# schematic.net
KiCad netlist of a schematic drawn in Altium Designer
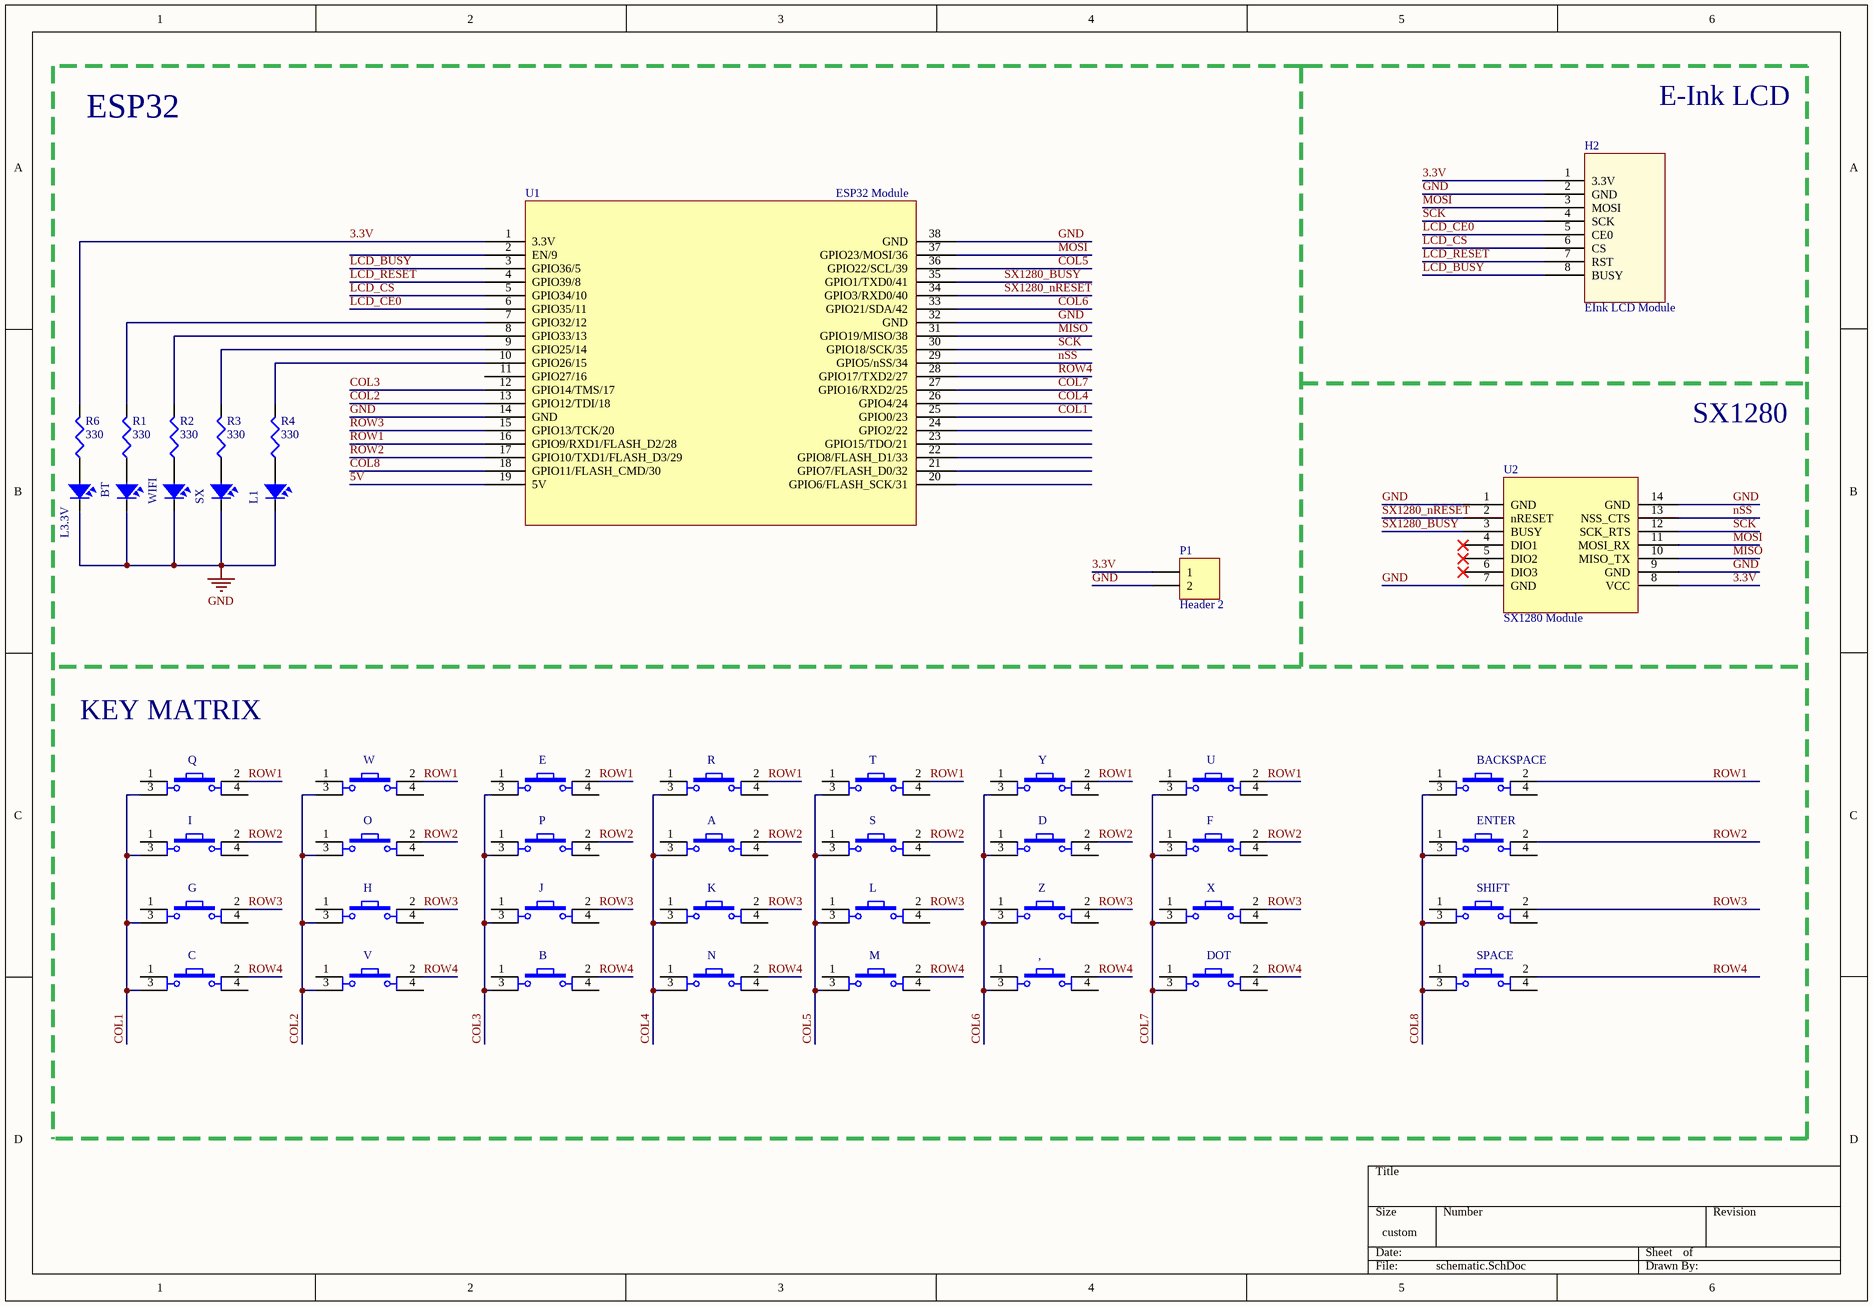
[diagram p0: schematic.SchDoc]

(export (version "E")
  (design (tool "Eeschema 10.0.6"))
  (components
    (comp (ref ",")
      (value "SW")
      (footprint "Kha_Button")
      (description "Switch button 4 pin")
      (libsource (lib "syhaunguyen") (part "SW4"))
    )
    (comp (ref "A")
      (value "SW")
      (footprint "Kha_Button")
      (description "Switch button 4 pin")
      (libsource (lib "syhaunguyen") (part "SW4"))
    )
    (comp (ref "B")
      (value "SW")
      (footprint "Kha_Button")
      (description "Switch button 4 pin")
      (libsource (lib "syhaunguyen") (part "SW4"))
    )
    (comp (ref "BACKSPACE")
      (value "SW")
      (footprint "Kha_Button")
      (description "Switch button 4 pin")
      (libsource (lib "syhaunguyen") (part "SW4"))
    )
    (comp (ref "BT")
      (value "LED SMD")
      (footprint "SM-LED-0805-Blue")
      (libsource (lib "syhaunguyen") (part "LED-SMD-0805"))
    )
    (comp (ref "C")
      (value "SW")
      (footprint "Kha_Button")
      (description "Switch button 4 pin")
      (libsource (lib "syhaunguyen") (part "SW4"))
    )
    (comp (ref "D")
      (value "SW")
      (footprint "Kha_Button")
      (description "Switch button 4 pin")
      (libsource (lib "syhaunguyen") (part "SW4"))
    )
    (comp (ref "DOT")
      (value "SW")
      (footprint "Kha_Button")
      (description "Switch button 4 pin")
      (libsource (lib "syhaunguyen") (part "SW4"))
    )
    (comp (ref "E")
      (value "SW")
      (footprint "Kha_Button")
      (description "Switch button 4 pin")
      (libsource (lib "syhaunguyen") (part "SW4"))
    )
    (comp (ref "ENTER")
      (value "SW")
      (footprint "Kha_Button")
      (description "Switch button 4 pin")
      (libsource (lib "syhaunguyen") (part "SW4"))
    )
    (comp (ref "F")
      (value "SW")
      (footprint "Kha_Button")
      (description "Switch button 4 pin")
      (libsource (lib "syhaunguyen") (part "SW4"))
    )
    (comp (ref "G")
      (value "SW")
      (footprint "Kha_Button")
      (description "Switch button 4 pin")
      (libsource (lib "syhaunguyen") (part "SW4"))
    )
    (comp (ref "H")
      (value "SW")
      (footprint "Kha_Button")
      (description "Switch button 4 pin")
      (libsource (lib "syhaunguyen") (part "SW4"))
    )
    (comp (ref "H2")
      (value "EInk LCD Module")
      (footprint "EInk_Module")
      (libsource (lib "EInk_Project_Lib") (part "E-Ink LCD"))
    )
    (comp (ref "I")
      (value "SW")
      (footprint "Kha_Button")
      (description "Switch button 4 pin")
      (libsource (lib "syhaunguyen") (part "SW4"))
    )
    (comp (ref "J")
      (value "SW")
      (footprint "Kha_Button")
      (description "Switch button 4 pin")
      (libsource (lib "syhaunguyen") (part "SW4"))
    )
    (comp (ref "K")
      (value "SW")
      (footprint "Kha_Button")
      (description "Switch button 4 pin")
      (libsource (lib "syhaunguyen") (part "SW4"))
    )
    (comp (ref "L")
      (value "SW")
      (footprint "Kha_Button")
      (description "Switch button 4 pin")
      (libsource (lib "syhaunguyen") (part "SW4"))
    )
    (comp (ref "L1")
      (value "LED SMD")
      (footprint "SM-LED-0805-Blue")
      (libsource (lib "syhaunguyen") (part "LED-SMD-0805"))
    )
    (comp (ref "L3.3V")
      (value "LED SMD")
      (footprint "SM-LED-0805-Blue")
      (libsource (lib "syhaunguyen") (part "LED-SMD-0805"))
    )
    (comp (ref "M")
      (value "SW")
      (footprint "Kha_Button")
      (description "Switch button 4 pin")
      (libsource (lib "syhaunguyen") (part "SW4"))
    )
    (comp (ref "N")
      (value "SW")
      (footprint "Kha_Button")
      (description "Switch button 4 pin")
      (libsource (lib "syhaunguyen") (part "SW4"))
    )
    (comp (ref "O")
      (value "SW")
      (footprint "Kha_Button")
      (description "Switch button 4 pin")
      (libsource (lib "syhaunguyen") (part "SW4"))
    )
    (comp (ref "P")
      (value "SW")
      (footprint "Kha_Button")
      (description "Switch button 4 pin")
      (libsource (lib "syhaunguyen") (part "SW4"))
    )
    (comp (ref "P1")
      (value "Header 2")
      (footprint "Header 2 SMT")
      (description "Header, 2-Pin")
      (fields (field (name "PUBLISHER") "Altium Limited"))
      (libsource (lib "Miscellaneous Connectors") (part "Header 2"))
    )
    (comp (ref "Q")
      (value "SW")
      (footprint "Kha_Button")
      (description "Switch button 4 pin")
      (libsource (lib "syhaunguyen") (part "SW4"))
    )
    (comp (ref "R")
      (value "SW")
      (footprint "Kha_Button")
      (description "Switch button 4 pin")
      (libsource (lib "syhaunguyen") (part "SW4"))
    )
    (comp (ref "R1")
      (value "330")
      (footprint "J1-0603")
      (description "Resistor")
      (fields (field (name "Comment") "Res3") (field (name "PUBLISHER") "Altium Limited"))
      (libsource (lib "Miscellaneous Devices") (part "Res3"))
    )
    (comp (ref "R2")
      (value "330")
      (footprint "J1-0603")
      (description "Resistor")
      (fields (field (name "Comment") "Res3") (field (name "PUBLISHER") "Altium Limited"))
      (libsource (lib "Miscellaneous Devices") (part "Res3"))
    )
    (comp (ref "R3")
      (value "330")
      (footprint "J1-0603")
      (description "Resistor")
      (fields (field (name "Comment") "Res3") (field (name "PUBLISHER") "Altium Limited"))
      (libsource (lib "Miscellaneous Devices") (part "Res3"))
    )
    (comp (ref "R4")
      (value "330")
      (footprint "J1-0603")
      (description "Resistor")
      (fields (field (name "Comment") "Res3") (field (name "PUBLISHER") "Altium Limited"))
      (libsource (lib "Miscellaneous Devices") (part "Res3"))
    )
    (comp (ref "R6")
      (value "330")
      (footprint "J1-0603")
      (description "Resistor")
      (fields (field (name "Comment") "Res3") (field (name "PUBLISHER") "Altium Limited"))
      (libsource (lib "Miscellaneous Devices") (part "Res3"))
    )
    (comp (ref "S")
      (value "SW")
      (footprint "Kha_Button")
      (description "Switch button 4 pin")
      (libsource (lib "syhaunguyen") (part "SW4"))
    )
    (comp (ref "SHIFT")
      (value "SW")
      (footprint "Kha_Button")
      (description "Switch button 4 pin")
      (libsource (lib "syhaunguyen") (part "SW4"))
    )
    (comp (ref "SPACE")
      (value "SW")
      (footprint "Kha_Button")
      (description "Switch button 4 pin")
      (libsource (lib "syhaunguyen") (part "SW4"))
    )
    (comp (ref "SX")
      (value "LED SMD")
      (footprint "SM-LED-0805-Blue")
      (libsource (lib "syhaunguyen") (part "LED-SMD-0805"))
    )
    (comp (ref "T")
      (value "SW")
      (footprint "Kha_Button")
      (description "Switch button 4 pin")
      (libsource (lib "syhaunguyen") (part "SW4"))
    )
    (comp (ref "U")
      (value "SW")
      (footprint "Kha_Button")
      (description "Switch button 4 pin")
      (libsource (lib "syhaunguyen") (part "SW4"))
    )
    (comp (ref "U1")
      (value "ESP32 Module")
      (footprint "ESP2 Module")
      (libsource (lib "EInk_Project_Lib") (part "ESP32_Module"))
    )
    (comp (ref "U2")
      (value "SX1280 Module")
      (footprint "SX1280 Module")
      (libsource (lib "EInk_Project_Lib") (part "SX1280 Module"))
    )
    (comp (ref "V")
      (value "SW")
      (footprint "Kha_Button")
      (description "Switch button 4 pin")
      (libsource (lib "syhaunguyen") (part "SW4"))
    )
    (comp (ref "W")
      (value "SW")
      (footprint "Kha_Button")
      (description "Switch button 4 pin")
      (libsource (lib "syhaunguyen") (part "SW4"))
    )
    (comp (ref "WIFI")
      (value "LED SMD")
      (footprint "SM-LED-0805-Blue")
      (libsource (lib "syhaunguyen") (part "LED-SMD-0805"))
    )
    (comp (ref "X")
      (value "SW")
      (footprint "Kha_Button")
      (description "Switch button 4 pin")
      (libsource (lib "syhaunguyen") (part "SW4"))
    )
    (comp (ref "Y")
      (value "SW")
      (footprint "Kha_Button")
      (description "Switch button 4 pin")
      (libsource (lib "syhaunguyen") (part "SW4"))
    )
    (comp (ref "Z")
      (value "SW")
      (footprint "Kha_Button")
      (description "Switch button 4 pin")
      (libsource (lib "syhaunguyen") (part "SW4"))
    )
  )
  (nets
    (net (code "1") (name "/3.3V") (class "Default")
      (node (ref "H2") (pin "1") (pinfunction "3.3V_1") (pintype "passive"))
      (node (ref "P1") (pin "1") (pinfunction "1_1") (pintype "passive"))
      (node (ref "R6") (pin "2") (pinfunction "2_2") (pintype "passive"))
      (node (ref "U1") (pin "1") (pinfunction "3.3V_1") (pintype "passive"))
      (node (ref "U2") (pin "8") (pinfunction "VCC_8") (pintype "passive"))
    )
    (net (code "2") (name "/5V") (class "Default")
      (node (ref "U1") (pin "19") (pinfunction "5V_19") (pintype "passive"))
    )
    (net (code "3") (name "/COL1") (class "Default")
      (node (ref "C") (pin "3") (pintype "passive"))
      (node (ref "G") (pin "3") (pintype "passive"))
      (node (ref "I") (pin "3") (pintype "passive"))
      (node (ref "Q") (pin "3") (pintype "passive"))
      (node (ref "U1") (pin "25") (pinfunction "GPIO0/23_25") (pintype "passive"))
    )
    (net (code "4") (name "/COL2") (class "Default")
      (node (ref "H") (pin "3") (pintype "passive"))
      (node (ref "O") (pin "3") (pintype "passive"))
      (node (ref "U1") (pin "13") (pinfunction "GPIO12/TDI/18_13") (pintype "passive"))
      (node (ref "V") (pin "3") (pintype "passive"))
      (node (ref "W") (pin "3") (pintype "passive"))
    )
    (net (code "5") (name "/COL3") (class "Default")
      (node (ref "B") (pin "3") (pintype "passive"))
      (node (ref "E") (pin "3") (pintype "passive"))
      (node (ref "J") (pin "3") (pintype "passive"))
      (node (ref "P") (pin "3") (pintype "passive"))
      (node (ref "U1") (pin "12") (pinfunction "GPIO14/TMS/17_12") (pintype "passive"))
    )
    (net (code "6") (name "/COL4") (class "Default")
      (node (ref "A") (pin "3") (pintype "passive"))
      (node (ref "K") (pin "3") (pintype "passive"))
      (node (ref "N") (pin "3") (pintype "passive"))
      (node (ref "R") (pin "3") (pintype "passive"))
      (node (ref "U1") (pin "26") (pinfunction "GPIO4/24_26") (pintype "passive"))
    )
    (net (code "7") (name "/COL5") (class "Default")
      (node (ref "L") (pin "3") (pintype "passive"))
      (node (ref "M") (pin "3") (pintype "passive"))
      (node (ref "S") (pin "3") (pintype "passive"))
      (node (ref "T") (pin "3") (pintype "passive"))
      (node (ref "U1") (pin "36") (pinfunction "GPIO22/SCL/39_36") (pintype "passive"))
    )
    (net (code "8") (name "/COL6") (class "Default")
      (node (ref ",") (pin "3") (pintype "passive"))
      (node (ref "D") (pin "3") (pintype "passive"))
      (node (ref "U1") (pin "33") (pinfunction "GPIO21/SDA/42_33") (pintype "passive"))
      (node (ref "Y") (pin "3") (pintype "passive"))
      (node (ref "Z") (pin "3") (pintype "passive"))
    )
    (net (code "9") (name "/COL7") (class "Default")
      (node (ref "DOT") (pin "3") (pintype "passive"))
      (node (ref "F") (pin "3") (pintype "passive"))
      (node (ref "U") (pin "3") (pintype "passive"))
      (node (ref "U1") (pin "27") (pinfunction "GPIO16/RXD2/25_27") (pintype "passive"))
      (node (ref "X") (pin "3") (pintype "passive"))
    )
    (net (code "10") (name "/COL8") (class "Default")
      (node (ref "BACKSPACE") (pin "3") (pintype "passive"))
      (node (ref "ENTER") (pin "3") (pintype "passive"))
      (node (ref "SHIFT") (pin "3") (pintype "passive"))
      (node (ref "SPACE") (pin "3") (pintype "passive"))
      (node (ref "U1") (pin "18") (pinfunction "GPIO11/FLASH_CMD/30_18") (pintype "passive"))
    )
    (net (code "11") (name "/LCD_BUSY") (class "Default")
      (node (ref "H2") (pin "8") (pinfunction "BUSY_8") (pintype "passive"))
      (node (ref "U1") (pin "3") (pinfunction "GPIO36/5_3") (pintype "passive"))
    )
    (net (code "12") (name "/LCD_CE0") (class "Default")
      (node (ref "H2") (pin "5") (pinfunction "CE0_5") (pintype "passive"))
      (node (ref "U1") (pin "6") (pinfunction "GPIO35/11_6") (pintype "passive"))
    )
    (net (code "13") (name "/LCD_CS") (class "Default")
      (node (ref "H2") (pin "6") (pinfunction "CS_6") (pintype "passive"))
      (node (ref "U1") (pin "5") (pinfunction "GPIO34/10_5") (pintype "passive"))
    )
    (net (code "14") (name "/LCD_RESET") (class "Default")
      (node (ref "H2") (pin "7") (pinfunction "RST_7") (pintype "passive"))
      (node (ref "U1") (pin "4") (pinfunction "GPIO39/8_4") (pintype "passive"))
    )
    (net (code "15") (name "/MISO") (class "Default")
      (node (ref "U1") (pin "31") (pinfunction "GPIO19/MISO/38_31") (pintype "passive"))
      (node (ref "U2") (pin "10") (pinfunction "MISO_TX_10") (pintype "passive"))
    )
    (net (code "16") (name "/MOSI") (class "Default")
      (node (ref "H2") (pin "3") (pinfunction "MOSI_3") (pintype "passive"))
      (node (ref "U1") (pin "37") (pinfunction "GPIO23/MOSI/36_37") (pintype "passive"))
      (node (ref "U2") (pin "11") (pinfunction "MOSI_RX_11") (pintype "passive"))
    )
    (net (code "17") (name "/ROW1") (class "Default")
      (node (ref "BACKSPACE") (pin "2") (pintype "passive"))
      (node (ref "E") (pin "2") (pintype "passive"))
      (node (ref "Q") (pin "2") (pintype "passive"))
      (node (ref "R") (pin "2") (pintype "passive"))
      (node (ref "T") (pin "2") (pintype "passive"))
      (node (ref "U") (pin "2") (pintype "passive"))
      (node (ref "U1") (pin "16") (pinfunction "GPIO9/RXD1/FLASH_D2/28_16") (pintype "passive"))
      (node (ref "W") (pin "2") (pintype "passive"))
      (node (ref "Y") (pin "2") (pintype "passive"))
    )
    (net (code "18") (name "/ROW2") (class "Default")
      (node (ref "A") (pin "2") (pintype "passive"))
      (node (ref "D") (pin "2") (pintype "passive"))
      (node (ref "ENTER") (pin "2") (pintype "passive"))
      (node (ref "F") (pin "2") (pintype "passive"))
      (node (ref "I") (pin "2") (pintype "passive"))
      (node (ref "O") (pin "2") (pintype "passive"))
      (node (ref "P") (pin "2") (pintype "passive"))
      (node (ref "S") (pin "2") (pintype "passive"))
      (node (ref "U1") (pin "17") (pinfunction "GPIO10/TXD1/FLASH_D3/29_17") (pintype "passive"))
    )
    (net (code "19") (name "/ROW3") (class "Default")
      (node (ref "G") (pin "2") (pintype "passive"))
      (node (ref "H") (pin "2") (pintype "passive"))
      (node (ref "J") (pin "2") (pintype "passive"))
      (node (ref "K") (pin "2") (pintype "passive"))
      (node (ref "L") (pin "2") (pintype "passive"))
      (node (ref "SHIFT") (pin "2") (pintype "passive"))
      (node (ref "U1") (pin "15") (pinfunction "GPIO13/TCK/20_15") (pintype "passive"))
      (node (ref "X") (pin "2") (pintype "passive"))
      (node (ref "Z") (pin "2") (pintype "passive"))
    )
    (net (code "20") (name "/ROW4") (class "Default")
      (node (ref ",") (pin "2") (pintype "passive"))
      (node (ref "B") (pin "2") (pintype "passive"))
      (node (ref "C") (pin "2") (pintype "passive"))
      (node (ref "DOT") (pin "2") (pintype "passive"))
      (node (ref "M") (pin "2") (pintype "passive"))
      (node (ref "N") (pin "2") (pintype "passive"))
      (node (ref "SPACE") (pin "2") (pintype "passive"))
      (node (ref "U1") (pin "28") (pinfunction "GPIO17/TXD2/27_28") (pintype "passive"))
      (node (ref "V") (pin "2") (pintype "passive"))
    )
    (net (code "21") (name "/SCK") (class "Default")
      (node (ref "H2") (pin "4") (pinfunction "SCK_4") (pintype "passive"))
      (node (ref "U1") (pin "30") (pinfunction "GPIO18/SCK/35_30") (pintype "passive"))
      (node (ref "U2") (pin "12") (pinfunction "SCK_RTS_12") (pintype "passive"))
    )
    (net (code "22") (name "/SX1280_BUSY") (class "Default")
      (node (ref "U1") (pin "35") (pinfunction "GPIO1/TXD0/41_35") (pintype "passive"))
      (node (ref "U2") (pin "3") (pinfunction "BUSY_3") (pintype "passive"))
    )
    (net (code "23") (name "/SX1280_nRESET") (class "Default")
      (node (ref "U1") (pin "34") (pinfunction "GPIO3/RXD0/40_34") (pintype "passive"))
      (node (ref "U2") (pin "2") (pinfunction "nRESET_2") (pintype "passive"))
    )
    (net (code "24") (name "/nSS") (class "Default")
      (node (ref "U1") (pin "29") (pinfunction "GPIO5/nSS/34_29") (pintype "passive"))
      (node (ref "U2") (pin "13") (pinfunction "NSS_CTS_13") (pintype "passive"))
    )
    (net (code "25") (name "GND") (class "Default")
      (node (ref "BT") (pin "2") (pinfunction "2_2") (pintype "passive"))
      (node (ref "H2") (pin "2") (pinfunction "GND_2") (pintype "passive"))
      (node (ref "L1") (pin "2") (pinfunction "2_2") (pintype "passive"))
      (node (ref "L3.3V") (pin "2") (pinfunction "2_2") (pintype "passive"))
      (node (ref "P1") (pin "2") (pinfunction "2_2") (pintype "passive"))
      (node (ref "SX") (pin "2") (pinfunction "2_2") (pintype "passive"))
      (node (ref "U1") (pin "14") (pinfunction "GND_14") (pintype "passive"))
      (node (ref "U1") (pin "32") (pinfunction "GND_32") (pintype "passive"))
      (node (ref "U1") (pin "38") (pinfunction "GND_38") (pintype "passive"))
      (node (ref "U2") (pin "1") (pinfunction "GND_1") (pintype "passive"))
      (node (ref "U2") (pin "14") (pinfunction "GND_14") (pintype "passive"))
      (node (ref "U2") (pin "7") (pinfunction "GND_7") (pintype "passive"))
      (node (ref "U2") (pin "9") (pinfunction "GND_9") (pintype "passive"))
      (node (ref "WIFI") (pin "2") (pinfunction "2_2") (pintype "passive"))
    )
    (net (code "26") (name "Net-(BT-Pad1)") (class "Default")
      (node (ref "BT") (pin "1") (pinfunction "1_1") (pintype "passive"))
      (node (ref "R1") (pin "1") (pinfunction "1_1") (pintype "passive"))
    )
    (net (code "27") (name "Net-(L1-Pad1)") (class "Default")
      (node (ref "L1") (pin "1") (pinfunction "1_1") (pintype "passive"))
      (node (ref "R4") (pin "1") (pinfunction "1_1") (pintype "passive"))
    )
    (net (code "28") (name "Net-(L3.3V-Pad1)") (class "Default")
      (node (ref "L3.3V") (pin "1") (pinfunction "1_1") (pintype "passive"))
      (node (ref "R6") (pin "1") (pinfunction "1_1") (pintype "passive"))
    )
    (net (code "29") (name "Net-(R2-Pad1)") (class "Default")
      (node (ref "R2") (pin "1") (pinfunction "1_1") (pintype "passive"))
      (node (ref "WIFI") (pin "1") (pinfunction "1_1") (pintype "passive"))
    )
    (net (code "30") (name "Net-(R3-Pad1)") (class "Default")
      (node (ref "R3") (pin "1") (pinfunction "1_1") (pintype "passive"))
      (node (ref "SX") (pin "1") (pinfunction "1_1") (pintype "passive"))
    )
    (net (code "31") (name "Net-(U1-GPIO25{slash}14)") (class "Default")
      (node (ref "R3") (pin "2") (pinfunction "2_2") (pintype "passive"))
      (node (ref "U1") (pin "9") (pinfunction "GPIO25/14_9") (pintype "passive"))
    )
    (net (code "32") (name "Net-(U1-GPIO26{slash}15)") (class "Default")
      (node (ref "R4") (pin "2") (pinfunction "2_2") (pintype "passive"))
      (node (ref "U1") (pin "10") (pinfunction "GPIO26/15_10") (pintype "passive"))
    )
    (net (code "33") (name "Net-(U1-GPIO32{slash}12)") (class "Default")
      (node (ref "R1") (pin "2") (pinfunction "2_2") (pintype "passive"))
      (node (ref "U1") (pin "7") (pinfunction "GPIO32/12_7") (pintype "passive"))
    )
    (net (code "34") (name "Net-(U1-GPIO33{slash}13)") (class "Default")
      (node (ref "R2") (pin "2") (pinfunction "2_2") (pintype "passive"))
      (node (ref "U1") (pin "8") (pinfunction "GPIO33/13_8") (pintype "passive"))
    )
    (net (code "35") (name "unconnected-(,-Pad1)") (class "Default")
      (node (ref ",") (pin "1") (pintype "passive"))
    )
    (net (code "36") (name "unconnected-(,-Pad4)") (class "Default")
      (node (ref ",") (pin "4") (pintype "passive"))
    )
    (net (code "37") (name "unconnected-(A-Pad1)") (class "Default")
      (node (ref "A") (pin "1") (pintype "passive"))
    )
    (net (code "38") (name "unconnected-(A-Pad4)") (class "Default")
      (node (ref "A") (pin "4") (pintype "passive"))
    )
    (net (code "39") (name "unconnected-(B-Pad1)") (class "Default")
      (node (ref "B") (pin "1") (pintype "passive"))
    )
    (net (code "40") (name "unconnected-(B-Pad4)") (class "Default")
      (node (ref "B") (pin "4") (pintype "passive"))
    )
    (net (code "41") (name "unconnected-(BACKSPACE-Pad1)") (class "Default")
      (node (ref "BACKSPACE") (pin "1") (pintype "passive"))
    )
    (net (code "42") (name "unconnected-(BACKSPACE-Pad4)") (class "Default")
      (node (ref "BACKSPACE") (pin "4") (pintype "passive"))
    )
    (net (code "43") (name "unconnected-(C-Pad1)") (class "Default")
      (node (ref "C") (pin "1") (pintype "passive"))
    )
    (net (code "44") (name "unconnected-(C-Pad4)") (class "Default")
      (node (ref "C") (pin "4") (pintype "passive"))
    )
    (net (code "45") (name "unconnected-(D-Pad1)") (class "Default")
      (node (ref "D") (pin "1") (pintype "passive"))
    )
    (net (code "46") (name "unconnected-(D-Pad4)") (class "Default")
      (node (ref "D") (pin "4") (pintype "passive"))
    )
    (net (code "47") (name "unconnected-(DOT-Pad1)") (class "Default")
      (node (ref "DOT") (pin "1") (pintype "passive"))
    )
    (net (code "48") (name "unconnected-(DOT-Pad4)") (class "Default")
      (node (ref "DOT") (pin "4") (pintype "passive"))
    )
    (net (code "49") (name "unconnected-(E-Pad1)") (class "Default")
      (node (ref "E") (pin "1") (pintype "passive"))
    )
    (net (code "50") (name "unconnected-(E-Pad4)") (class "Default")
      (node (ref "E") (pin "4") (pintype "passive"))
    )
    (net (code "51") (name "unconnected-(ENTER-Pad1)") (class "Default")
      (node (ref "ENTER") (pin "1") (pintype "passive"))
    )
    (net (code "52") (name "unconnected-(ENTER-Pad4)") (class "Default")
      (node (ref "ENTER") (pin "4") (pintype "passive"))
    )
    (net (code "53") (name "unconnected-(F-Pad1)") (class "Default")
      (node (ref "F") (pin "1") (pintype "passive"))
    )
    (net (code "54") (name "unconnected-(F-Pad4)") (class "Default")
      (node (ref "F") (pin "4") (pintype "passive"))
    )
    (net (code "55") (name "unconnected-(G-Pad1)") (class "Default")
      (node (ref "G") (pin "1") (pintype "passive"))
    )
    (net (code "56") (name "unconnected-(G-Pad4)") (class "Default")
      (node (ref "G") (pin "4") (pintype "passive"))
    )
    (net (code "57") (name "unconnected-(H-Pad1)") (class "Default")
      (node (ref "H") (pin "1") (pintype "passive"))
    )
    (net (code "58") (name "unconnected-(H-Pad4)") (class "Default")
      (node (ref "H") (pin "4") (pintype "passive"))
    )
    (net (code "59") (name "unconnected-(I-Pad1)") (class "Default")
      (node (ref "I") (pin "1") (pintype "passive"))
    )
    (net (code "60") (name "unconnected-(I-Pad4)") (class "Default")
      (node (ref "I") (pin "4") (pintype "passive"))
    )
    (net (code "61") (name "unconnected-(J-Pad1)") (class "Default")
      (node (ref "J") (pin "1") (pintype "passive"))
    )
    (net (code "62") (name "unconnected-(J-Pad4)") (class "Default")
      (node (ref "J") (pin "4") (pintype "passive"))
    )
    (net (code "63") (name "unconnected-(K-Pad1)") (class "Default")
      (node (ref "K") (pin "1") (pintype "passive"))
    )
    (net (code "64") (name "unconnected-(K-Pad4)") (class "Default")
      (node (ref "K") (pin "4") (pintype "passive"))
    )
    (net (code "65") (name "unconnected-(L-Pad1)") (class "Default")
      (node (ref "L") (pin "1") (pintype "passive"))
    )
    (net (code "66") (name "unconnected-(L-Pad4)") (class "Default")
      (node (ref "L") (pin "4") (pintype "passive"))
    )
    (net (code "67") (name "unconnected-(M-Pad1)") (class "Default")
      (node (ref "M") (pin "1") (pintype "passive"))
    )
    (net (code "68") (name "unconnected-(M-Pad4)") (class "Default")
      (node (ref "M") (pin "4") (pintype "passive"))
    )
    (net (code "69") (name "unconnected-(N-Pad1)") (class "Default")
      (node (ref "N") (pin "1") (pintype "passive"))
    )
    (net (code "70") (name "unconnected-(N-Pad4)") (class "Default")
      (node (ref "N") (pin "4") (pintype "passive"))
    )
    (net (code "71") (name "unconnected-(O-Pad1)") (class "Default")
      (node (ref "O") (pin "1") (pintype "passive"))
    )
    (net (code "72") (name "unconnected-(O-Pad4)") (class "Default")
      (node (ref "O") (pin "4") (pintype "passive"))
    )
    (net (code "73") (name "unconnected-(P-Pad1)") (class "Default")
      (node (ref "P") (pin "1") (pintype "passive"))
    )
    (net (code "74") (name "unconnected-(P-Pad4)") (class "Default")
      (node (ref "P") (pin "4") (pintype "passive"))
    )
    (net (code "75") (name "unconnected-(Q-Pad1)") (class "Default")
      (node (ref "Q") (pin "1") (pintype "passive"))
    )
    (net (code "76") (name "unconnected-(Q-Pad4)") (class "Default")
      (node (ref "Q") (pin "4") (pintype "passive"))
    )
    (net (code "77") (name "unconnected-(R-Pad1)") (class "Default")
      (node (ref "R") (pin "1") (pintype "passive"))
    )
    (net (code "78") (name "unconnected-(R-Pad4)") (class "Default")
      (node (ref "R") (pin "4") (pintype "passive"))
    )
    (net (code "79") (name "unconnected-(S-Pad1)") (class "Default")
      (node (ref "S") (pin "1") (pintype "passive"))
    )
    (net (code "80") (name "unconnected-(S-Pad4)") (class "Default")
      (node (ref "S") (pin "4") (pintype "passive"))
    )
    (net (code "81") (name "unconnected-(SHIFT-Pad1)") (class "Default")
      (node (ref "SHIFT") (pin "1") (pintype "passive"))
    )
    (net (code "82") (name "unconnected-(SHIFT-Pad4)") (class "Default")
      (node (ref "SHIFT") (pin "4") (pintype "passive"))
    )
    (net (code "83") (name "unconnected-(SPACE-Pad1)") (class "Default")
      (node (ref "SPACE") (pin "1") (pintype "passive"))
    )
    (net (code "84") (name "unconnected-(SPACE-Pad4)") (class "Default")
      (node (ref "SPACE") (pin "4") (pintype "passive"))
    )
    (net (code "85") (name "unconnected-(T-Pad1)") (class "Default")
      (node (ref "T") (pin "1") (pintype "passive"))
    )
    (net (code "86") (name "unconnected-(T-Pad4)") (class "Default")
      (node (ref "T") (pin "4") (pintype "passive"))
    )
    (net (code "87") (name "unconnected-(U-Pad1)") (class "Default")
      (node (ref "U") (pin "1") (pintype "passive"))
    )
    (net (code "88") (name "unconnected-(U-Pad4)") (class "Default")
      (node (ref "U") (pin "4") (pintype "passive"))
    )
    (net (code "89") (name "unconnected-(U1-EN{slash}9-Pad2)") (class "Default")
      (node (ref "U1") (pin "2") (pinfunction "EN/9_2") (pintype "passive"))
    )
    (net (code "90") (name "unconnected-(U1-GPIO2{slash}22-Pad24)") (class "Default")
      (node (ref "U1") (pin "24") (pinfunction "GPIO2/22_24") (pintype "passive"))
    )
    (net (code "91") (name "unconnected-(U1-GPIO6{slash}FLASH_SCK{slash}31-Pad20)") (class "Default")
      (node (ref "U1") (pin "20") (pinfunction "GPIO6/FLASH_SCK/31_20") (pintype "passive"))
    )
    (net (code "92") (name "unconnected-(U1-GPIO7{slash}FLASH_D0{slash}32-Pad21)") (class "Default")
      (node (ref "U1") (pin "21") (pinfunction "GPIO7/FLASH_D0/32_21") (pintype "passive"))
    )
    (net (code "93") (name "unconnected-(U1-GPIO8{slash}FLASH_D1{slash}33-Pad22)") (class "Default")
      (node (ref "U1") (pin "22") (pinfunction "GPIO8/FLASH_D1/33_22") (pintype "passive"))
    )
    (net (code "94") (name "unconnected-(U1-GPIO15{slash}TDO{slash}21-Pad23)") (class "Default")
      (node (ref "U1") (pin "23") (pinfunction "GPIO15/TDO/21_23") (pintype "passive"))
    )
    (net (code "95") (name "unconnected-(U1-GPIO27{slash}16-Pad11)") (class "Default")
      (node (ref "U1") (pin "11") (pinfunction "GPIO27/16_11") (pintype "passive"))
    )
    (net (code "96") (name "unconnected-(U2-DIO1-Pad4)") (class "Default")
      (node (ref "U2") (pin "4") (pinfunction "DIO1_4") (pintype "passive+no_connect"))
    )
    (net (code "97") (name "unconnected-(U2-DIO2-Pad5)") (class "Default")
      (node (ref "U2") (pin "5") (pinfunction "DIO2_5") (pintype "passive+no_connect"))
    )
    (net (code "98") (name "unconnected-(U2-DIO3-Pad6)") (class "Default")
      (node (ref "U2") (pin "6") (pinfunction "DIO3_6") (pintype "passive+no_connect"))
    )
    (net (code "99") (name "unconnected-(V-Pad1)") (class "Default")
      (node (ref "V") (pin "1") (pintype "passive"))
    )
    (net (code "100") (name "unconnected-(V-Pad4)") (class "Default")
      (node (ref "V") (pin "4") (pintype "passive"))
    )
    (net (code "101") (name "unconnected-(W-Pad1)") (class "Default")
      (node (ref "W") (pin "1") (pintype "passive"))
    )
    (net (code "102") (name "unconnected-(W-Pad4)") (class "Default")
      (node (ref "W") (pin "4") (pintype "passive"))
    )
    (net (code "103") (name "unconnected-(X-Pad1)") (class "Default")
      (node (ref "X") (pin "1") (pintype "passive"))
    )
    (net (code "104") (name "unconnected-(X-Pad4)") (class "Default")
      (node (ref "X") (pin "4") (pintype "passive"))
    )
    (net (code "105") (name "unconnected-(Y-Pad1)") (class "Default")
      (node (ref "Y") (pin "1") (pintype "passive"))
    )
    (net (code "106") (name "unconnected-(Y-Pad4)") (class "Default")
      (node (ref "Y") (pin "4") (pintype "passive"))
    )
    (net (code "107") (name "unconnected-(Z-Pad1)") (class "Default")
      (node (ref "Z") (pin "1") (pintype "passive"))
    )
    (net (code "108") (name "unconnected-(Z-Pad4)") (class "Default")
      (node (ref "Z") (pin "4") (pintype "passive"))
    )
  )
)
